# dac0808.net
KiCad netlist of a schematic drawn in Altium Designer
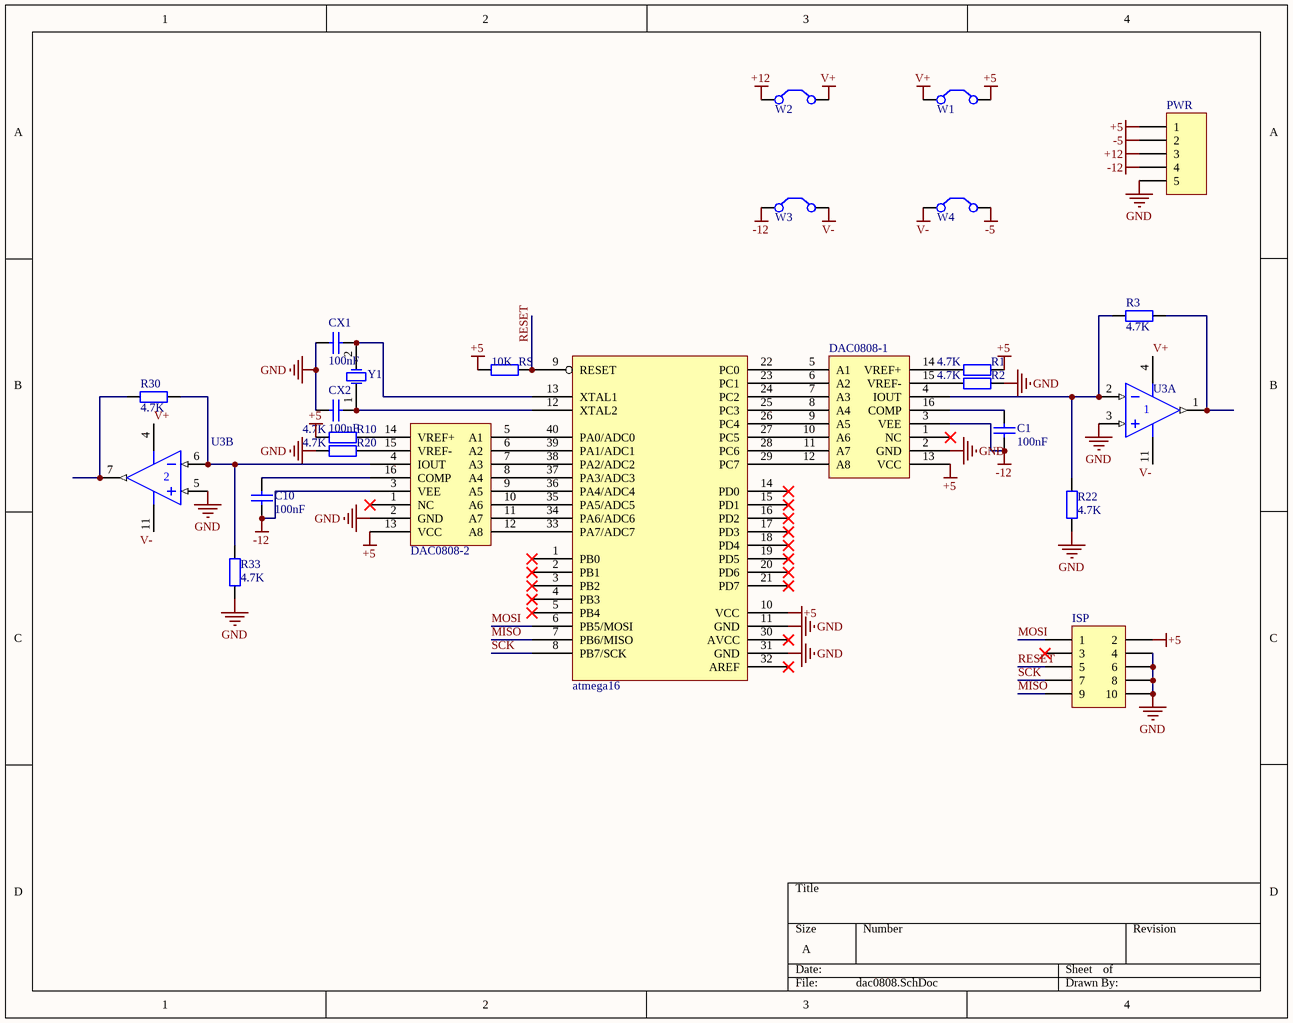
[diagram p0: dac0808.SchDoc]

(export (version "E")
  (design (tool "Eeschema 10.0.6"))
  (components
    (comp (ref "atmega16")
      (value "atmega16")
      (footprint "DIP-40PIN")
      (libsource (lib "atmega16") (part "atmega16"))
    )
    (comp (ref "C1")
      (value "100nF")
      (footprint "mkt")
      (description "Capacitor")
      (fields (field (name "Comment") "Cap") (field (name "PUBLISHER") "Altium Limited"))
      (libsource (lib "Miscellaneous Devices") (part "Cap"))
    )
    (comp (ref "C10")
      (value "100nF")
      (footprint "mkt")
      (description "Capacitor")
      (fields (field (name "Comment") "Cap") (field (name "PUBLISHER") "Altium Limited"))
      (libsource (lib "Miscellaneous Devices") (part "Cap"))
    )
    (comp (ref "CX1")
      (value "100nF")
      (footprint "mkt")
      (description "Capacitor")
      (fields (field (name "Comment") "Cap") (field (name "PUBLISHER") "Altium Limited"))
      (libsource (lib "Miscellaneous Devices") (part "Cap"))
    )
    (comp (ref "CX2")
      (value "100nF")
      (footprint "mkt")
      (description "Capacitor")
      (fields (field (name "Comment") "Cap") (field (name "PUBLISHER") "Altium Limited"))
      (libsource (lib "Miscellaneous Devices") (part "Cap"))
    )
    (comp (ref "DAC0808-1")
      (value "DAC0808")
      (footprint "DIP-16-1")
      (libsource (lib "DAC0808") (part "DAC0808"))
    )
    (comp (ref "DAC0808-2") (value "DAC0808") (footprint "DIP-16-1") (libsource (lib "") (part "DAC0808_1")))
    (comp (ref "ISP")
      (value "Header 5X2")
      (footprint "HDR2X5")
      (description "Header, 5-Pin, Dual row")
      (fields (field (name "PUBLISHER") "Altium Limited"))
      (libsource (lib "Miscellaneous Connectors") (part "Header 5X2"))
    )
    (comp (ref "PWR")
      (value "Header 5")
      (footprint "PWR")
      (description "Header, 5-Pin")
      (fields (field (name "PUBLISHER") "Altium Limited"))
      (libsource (lib "Miscellaneous Connectors") (part "Header 5"))
    )
    (comp (ref "R1")
      (value "4.7K")
      (footprint "AXIAL-0.4")
      (description "Resistor")
      (fields (field (name "Comment") "Res2") (field (name "PUBLISHER") "Altium Limited"))
      (libsource (lib "Miscellaneous Devices") (part "Res2"))
    )
    (comp (ref "R2")
      (value "4.7K")
      (footprint "AXIAL-0.4")
      (description "Resistor")
      (fields (field (name "Comment") "Res2") (field (name "PUBLISHER") "Altium Limited"))
      (libsource (lib "Miscellaneous Devices") (part "Res2"))
    )
    (comp (ref "R3")
      (value "4.7K")
      (footprint "AXIAL-0.4")
      (description "Resistor")
      (fields (field (name "Comment") "Res2") (field (name "PUBLISHER") "Altium Limited"))
      (libsource (lib "Miscellaneous Devices") (part "Res2"))
    )
    (comp (ref "R10")
      (value "4.7K")
      (footprint "AXIAL-0.4")
      (description "Resistor")
      (fields (field (name "Comment") "Res2") (field (name "PUBLISHER") "Altium Limited"))
      (libsource (lib "Miscellaneous Devices") (part "Res2"))
    )
    (comp (ref "R20")
      (value "4.7K")
      (footprint "AXIAL-0.4")
      (description "Resistor")
      (fields (field (name "Comment") "Res2") (field (name "PUBLISHER") "Altium Limited"))
      (libsource (lib "Miscellaneous Devices") (part "Res2"))
    )
    (comp (ref "R22")
      (value "4.7K")
      (footprint "AXIAL-0.4")
      (description "Resistor")
      (fields (field (name "Comment") "Res2") (field (name "PUBLISHER") "Altium Limited"))
      (libsource (lib "") (part "Res2_1"))
    )
    (comp (ref "R30")
      (value "4.7K")
      (footprint "AXIAL-0.4")
      (description "Resistor")
      (fields (field (name "Comment") "Res2") (field (name "PUBLISHER") "Altium Limited"))
      (libsource (lib "Miscellaneous Devices") (part "Res2"))
    )
    (comp (ref "R33")
      (value "4.7K")
      (footprint "AXIAL-0.4")
      (description "Resistor")
      (fields (field (name "Comment") "Res2") (field (name "PUBLISHER") "Altium Limited"))
      (libsource (lib "") (part "Res2_1"))
    )
    (comp (ref "RS")
      (value "10K")
      (footprint "AXIAL-0.4")
      (description "Resistor")
      (fields (field (name "Comment") "Res2") (field (name "PUBLISHER") "Altium Limited"))
      (libsource (lib "Miscellaneous Devices") (part "Res2"))
    )
    (comp (ref "U3")
      (value "LM324AJ")
      (footprint "J014")
      (description "Quadruple Operational Amplifier")
      (fields (field (name "PUBLISHER") "Altium Limited"))
      (libsource (lib "TI Operational Amplifier") (part "LM324AJ"))
    )
    (comp (ref "W1")
      (value "Jumper")
      (footprint "Miscellaneous Connectors:HDR1X2")
      (description "Jumper Wire")
      (fields (field (name "PUBLISHER") "Altium Limited"))
      (libsource (lib "Miscellaneous Devices") (part "Jumper"))
    )
    (comp (ref "W2")
      (value "Jumper")
      (footprint "Miscellaneous Connectors:HDR1X2")
      (description "Jumper Wire")
      (fields (field (name "PUBLISHER") "Altium Limited"))
      (libsource (lib "Miscellaneous Devices") (part "Jumper"))
    )
    (comp (ref "W3")
      (value "Jumper")
      (footprint "Miscellaneous Connectors:HDR1X2")
      (description "Jumper Wire")
      (fields (field (name "PUBLISHER") "Altium Limited"))
      (libsource (lib "Miscellaneous Devices") (part "Jumper"))
    )
    (comp (ref "W4")
      (value "Jumper")
      (footprint "Miscellaneous Connectors:HDR1X2")
      (description "Jumper Wire")
      (fields (field (name "PUBLISHER") "Altium Limited"))
      (libsource (lib "Miscellaneous Devices") (part "Jumper"))
    )
    (comp (ref "Y1")
      (value "XTAL")
      (footprint "XTAL")
      (description "Crystal Oscillator")
      (fields (field (name "PUBLISHER") "Altium Limited"))
      (libsource (lib "Miscellaneous Devices") (part "XTAL"))
    )
  )
  (nets
    (net (code "1") (name "+5") (class "Default")
      (node (ref "DAC0808-1") (pin "13") (pinfunction "VCC_13") (pintype "passive"))
      (node (ref "DAC0808-2") (pin "13") (pinfunction "VCC_13") (pintype "passive"))
      (node (ref "ISP") (pin "2") (pinfunction "2_2") (pintype "passive"))
      (node (ref "PWR") (pin "1") (pinfunction "1_1") (pintype "passive"))
      (node (ref "R1") (pin "2") (pinfunction "2_2") (pintype "passive"))
      (node (ref "R10") (pin "1") (pinfunction "1_1") (pintype "passive"))
      (node (ref "RS") (pin "1") (pinfunction "1_1") (pintype "passive"))
      (node (ref "W1") (pin "2") (pinfunction "C2_2") (pintype "passive"))
      (node (ref "atmega16") (pin "10") (pinfunction "VCC_10") (pintype "passive"))
    )
    (net (code "2") (name "+12") (class "Default")
      (node (ref "PWR") (pin "3") (pinfunction "3_3") (pintype "passive"))
      (node (ref "W2") (pin "1") (pinfunction "C1_1") (pintype "passive"))
    )
    (net (code "3") (name "-5") (class "Default")
      (node (ref "PWR") (pin "2") (pinfunction "2_2") (pintype "passive"))
      (node (ref "W4") (pin "2") (pinfunction "C2_2") (pintype "passive"))
    )
    (net (code "4") (name "-12") (class "Default")
      (node (ref "C1") (pin "1") (pinfunction "1_1") (pintype "passive"))
      (node (ref "C10") (pin "1") (pinfunction "1_1") (pintype "passive"))
      (node (ref "DAC0808-1") (pin "3") (pinfunction "VEE_3") (pintype "passive"))
      (node (ref "DAC0808-2") (pin "3") (pinfunction "VEE_3") (pintype "passive"))
      (node (ref "PWR") (pin "4") (pinfunction "4_4") (pintype "passive"))
      (node (ref "W3") (pin "1") (pinfunction "C1_1") (pintype "passive"))
    )
    (net (code "5") (name "/MISO") (class "Default")
      (node (ref "ISP") (pin "9") (pinfunction "9_9") (pintype "passive"))
      (node (ref "atmega16") (pin "7") (pinfunction "PB6/MISO_7") (pintype "passive"))
    )
    (net (code "6") (name "/MOSI") (class "Default")
      (node (ref "ISP") (pin "1") (pinfunction "1_1") (pintype "passive"))
      (node (ref "atmega16") (pin "6") (pinfunction "PB5/MOSI_6") (pintype "passive"))
    )
    (net (code "7") (name "/RESET") (class "Default")
      (node (ref "ISP") (pin "5") (pinfunction "5_5") (pintype "passive"))
      (node (ref "RS") (pin "2") (pinfunction "2_2") (pintype "passive"))
      (node (ref "atmega16") (pin "9") (pinfunction "RESET_9") (pintype "passive"))
    )
    (net (code "8") (name "/SCK") (class "Default")
      (node (ref "ISP") (pin "7") (pinfunction "7_7") (pintype "passive"))
      (node (ref "atmega16") (pin "8") (pinfunction "PB7/SCK_8") (pintype "passive"))
    )
    (net (code "9") (name "GND") (class "Default")
      (node (ref "CX1") (pin "1") (pinfunction "1_1") (pintype "passive"))
      (node (ref "CX2") (pin "1") (pinfunction "1_1") (pintype "passive"))
      (node (ref "DAC0808-1") (pin "2") (pinfunction "GND_2") (pintype "passive"))
      (node (ref "DAC0808-2") (pin "2") (pinfunction "GND_2") (pintype "passive"))
      (node (ref "ISP") (pin "10") (pinfunction "10_10") (pintype "passive"))
      (node (ref "ISP") (pin "4") (pinfunction "4_4") (pintype "passive"))
      (node (ref "ISP") (pin "6") (pinfunction "6_6") (pintype "passive"))
      (node (ref "ISP") (pin "8") (pinfunction "8_8") (pintype "passive"))
      (node (ref "PWR") (pin "5") (pinfunction "5_5") (pintype "passive"))
      (node (ref "R2") (pin "2") (pinfunction "2_2") (pintype "passive"))
      (node (ref "R20") (pin "1") (pinfunction "1_1") (pintype "passive"))
      (node (ref "R22") (pin "1") (pinfunction "1_1") (pintype "passive"))
      (node (ref "R33") (pin "1") (pinfunction "1_1") (pintype "passive"))
      (node (ref "U3") (pin "3") (pinfunction "IN+_3") (pintype "input"))
      (node (ref "U3") (pin "5") (pinfunction "IN+_5") (pintype "input"))
      (node (ref "atmega16") (pin "11") (pinfunction "GND_11") (pintype "passive"))
      (node (ref "atmega16") (pin "31") (pinfunction "GND_31") (pintype "passive"))
    )
    (net (code "10") (name "Net-(DAC0808-1-A1)") (class "Default")
      (node (ref "DAC0808-1") (pin "5") (pinfunction "A1_5") (pintype "passive"))
      (node (ref "atmega16") (pin "22") (pinfunction "PC0_22") (pintype "passive"))
    )
    (net (code "11") (name "Net-(DAC0808-1-A2)") (class "Default")
      (node (ref "DAC0808-1") (pin "6") (pinfunction "A2_6") (pintype "passive"))
      (node (ref "atmega16") (pin "23") (pinfunction "PC1_23") (pintype "passive"))
    )
    (net (code "12") (name "Net-(DAC0808-1-A3)") (class "Default")
      (node (ref "DAC0808-1") (pin "7") (pinfunction "A3_7") (pintype "passive"))
      (node (ref "atmega16") (pin "24") (pinfunction "PC2_24") (pintype "passive"))
    )
    (net (code "13") (name "Net-(DAC0808-1-A4)") (class "Default")
      (node (ref "DAC0808-1") (pin "8") (pinfunction "A4_8") (pintype "passive"))
      (node (ref "atmega16") (pin "25") (pinfunction "PC3_25") (pintype "passive"))
    )
    (net (code "14") (name "Net-(DAC0808-1-A5)") (class "Default")
      (node (ref "DAC0808-1") (pin "9") (pinfunction "A5_9") (pintype "passive"))
      (node (ref "atmega16") (pin "26") (pinfunction "PC4_26") (pintype "passive"))
    )
    (net (code "15") (name "Net-(DAC0808-1-A6)") (class "Default")
      (node (ref "DAC0808-1") (pin "10") (pinfunction "A6_10") (pintype "passive"))
      (node (ref "atmega16") (pin "27") (pinfunction "PC5_27") (pintype "passive"))
    )
    (net (code "16") (name "Net-(DAC0808-1-A7)") (class "Default")
      (node (ref "DAC0808-1") (pin "11") (pinfunction "A7_11") (pintype "passive"))
      (node (ref "atmega16") (pin "28") (pinfunction "PC6_28") (pintype "passive"))
    )
    (net (code "17") (name "Net-(DAC0808-1-A8)") (class "Default")
      (node (ref "DAC0808-1") (pin "12") (pinfunction "A8_12") (pintype "passive"))
      (node (ref "atmega16") (pin "29") (pinfunction "PC7_29") (pintype "passive"))
    )
    (net (code "18") (name "Net-(DAC0808-1-COMP)") (class "Default")
      (node (ref "C1") (pin "2") (pinfunction "2_2") (pintype "passive"))
      (node (ref "DAC0808-1") (pin "16") (pinfunction "COMP_16") (pintype "passive"))
    )
    (net (code "19") (name "Net-(DAC0808-1-IOUT)") (class "Default")
      (node (ref "DAC0808-1") (pin "4") (pinfunction "IOUT_4") (pintype "passive"))
      (node (ref "R22") (pin "2") (pinfunction "2_2") (pintype "passive"))
      (node (ref "R3") (pin "1") (pinfunction "1_1") (pintype "passive"))
      (node (ref "U3") (pin "2") (pinfunction "IN-_2") (pintype "input"))
    )
    (net (code "20") (name "Net-(DAC0808-1-VREF+)") (class "Default")
      (node (ref "DAC0808-1") (pin "14") (pinfunction "VREF+_14") (pintype "passive"))
      (node (ref "R1") (pin "1") (pinfunction "1_1") (pintype "passive"))
    )
    (net (code "21") (name "Net-(DAC0808-1-VREF-)") (class "Default")
      (node (ref "DAC0808-1") (pin "15") (pinfunction "VREF-_15") (pintype "passive"))
      (node (ref "R2") (pin "1") (pinfunction "1_1") (pintype "passive"))
    )
    (net (code "22") (name "Net-(DAC0808-2-A1)") (class "Default")
      (node (ref "DAC0808-2") (pin "5") (pinfunction "A1_5") (pintype "passive"))
      (node (ref "atmega16") (pin "40") (pinfunction "PA0/ADC0_40") (pintype "passive"))
    )
    (net (code "23") (name "Net-(DAC0808-2-A2)") (class "Default")
      (node (ref "DAC0808-2") (pin "6") (pinfunction "A2_6") (pintype "passive"))
      (node (ref "atmega16") (pin "39") (pinfunction "PA1/ADC1_39") (pintype "passive"))
    )
    (net (code "24") (name "Net-(DAC0808-2-A3)") (class "Default")
      (node (ref "DAC0808-2") (pin "7") (pinfunction "A3_7") (pintype "passive"))
      (node (ref "atmega16") (pin "38") (pinfunction "PA2/ADC2_38") (pintype "passive"))
    )
    (net (code "25") (name "Net-(DAC0808-2-A4)") (class "Default")
      (node (ref "DAC0808-2") (pin "8") (pinfunction "A4_8") (pintype "passive"))
      (node (ref "atmega16") (pin "37") (pinfunction "PA3/ADC3_37") (pintype "passive"))
    )
    (net (code "26") (name "Net-(DAC0808-2-A5)") (class "Default")
      (node (ref "DAC0808-2") (pin "9") (pinfunction "A5_9") (pintype "passive"))
      (node (ref "atmega16") (pin "36") (pinfunction "PA4/ADC4_36") (pintype "passive"))
    )
    (net (code "27") (name "Net-(DAC0808-2-A6)") (class "Default")
      (node (ref "DAC0808-2") (pin "10") (pinfunction "A6_10") (pintype "passive"))
      (node (ref "atmega16") (pin "35") (pinfunction "PA5/ADC5_35") (pintype "passive"))
    )
    (net (code "28") (name "Net-(DAC0808-2-A7)") (class "Default")
      (node (ref "DAC0808-2") (pin "11") (pinfunction "A7_11") (pintype "passive"))
      (node (ref "atmega16") (pin "34") (pinfunction "PA6/ADC6_34") (pintype "passive"))
    )
    (net (code "29") (name "Net-(DAC0808-2-A8)") (class "Default")
      (node (ref "DAC0808-2") (pin "12") (pinfunction "A8_12") (pintype "passive"))
      (node (ref "atmega16") (pin "33") (pinfunction "PA7/ADC7_33") (pintype "passive"))
    )
    (net (code "30") (name "Net-(DAC0808-2-COMP)") (class "Default")
      (node (ref "C10") (pin "2") (pinfunction "2_2") (pintype "passive"))
      (node (ref "DAC0808-2") (pin "16") (pinfunction "COMP_16") (pintype "passive"))
    )
    (net (code "31") (name "Net-(DAC0808-2-IOUT)") (class "Default")
      (node (ref "DAC0808-2") (pin "4") (pinfunction "IOUT_4") (pintype "passive"))
      (node (ref "R30") (pin "2") (pinfunction "2_2") (pintype "passive"))
      (node (ref "R33") (pin "2") (pinfunction "2_2") (pintype "passive"))
      (node (ref "U3") (pin "6") (pinfunction "IN-_6") (pintype "input"))
    )
    (net (code "32") (name "Net-(DAC0808-2-VREF+)") (class "Default")
      (node (ref "DAC0808-2") (pin "14") (pinfunction "VREF+_14") (pintype "passive"))
      (node (ref "R10") (pin "2") (pinfunction "2_2") (pintype "passive"))
    )
    (net (code "33") (name "Net-(DAC0808-2-VREF-)") (class "Default")
      (node (ref "DAC0808-2") (pin "15") (pinfunction "VREF-_15") (pintype "passive"))
      (node (ref "R20") (pin "2") (pinfunction "2_2") (pintype "passive"))
    )
    (net (code "34") (name "Net-(U3A-OUT)") (class "Default")
      (node (ref "R3") (pin "2") (pinfunction "2_2") (pintype "passive"))
      (node (ref "U3") (pin "1") (pinfunction "OUT_1") (pintype "output"))
    )
    (net (code "35") (name "Net-(U3B-OUT)") (class "Default")
      (node (ref "R30") (pin "1") (pinfunction "1_1") (pintype "passive"))
      (node (ref "U3") (pin "7") (pinfunction "OUT_7") (pintype "output"))
    )
    (net (code "36") (name "Net-(Y1-OSC1)") (class "Default")
      (node (ref "CX2") (pin "2") (pinfunction "2_2") (pintype "passive"))
      (node (ref "Y1") (pin "1") (pinfunction "OSC1_1") (pintype "passive"))
      (node (ref "atmega16") (pin "12") (pinfunction "XTAL2_12") (pintype "passive"))
    )
    (net (code "37") (name "Net-(Y1-OSC2)") (class "Default")
      (node (ref "CX1") (pin "2") (pinfunction "2_2") (pintype "passive"))
      (node (ref "Y1") (pin "2") (pinfunction "OSC2_2") (pintype "passive"))
      (node (ref "atmega16") (pin "13") (pinfunction "XTAL1_13") (pintype "passive"))
    )
    (net (code "38") (name "V+") (class "Default")
      (node (ref "U3") (pin "4") (pinfunction "V+_4") (pintype "power_in"))
      (node (ref "W1") (pin "1") (pinfunction "C1_1") (pintype "passive"))
      (node (ref "W2") (pin "2") (pinfunction "C2_2") (pintype "passive"))
    )
    (net (code "39") (name "V-") (class "Default")
      (node (ref "U3") (pin "11") (pinfunction "V-_11") (pintype "power_in"))
      (node (ref "W3") (pin "2") (pinfunction "C2_2") (pintype "passive"))
      (node (ref "W4") (pin "1") (pinfunction "C1_1") (pintype "passive"))
    )
    (net (code "40") (name "unconnected-(DAC0808-1-NC-Pad1)") (class "Default")
      (node (ref "DAC0808-1") (pin "1") (pinfunction "NC_1") (pintype "passive+no_connect"))
    )
    (net (code "41") (name "unconnected-(DAC0808-2-NC-Pad1)") (class "Default")
      (node (ref "DAC0808-2") (pin "1") (pinfunction "NC_1") (pintype "passive+no_connect"))
    )
    (net (code "42") (name "unconnected-(ISP-Pad3)") (class "Default")
      (node (ref "ISP") (pin "3") (pinfunction "3_3") (pintype "passive+no_connect"))
    )
    (net (code "43") (name "unconnected-(atmega16-AREF-Pad32)") (class "Default")
      (node (ref "atmega16") (pin "32") (pinfunction "AREF_32") (pintype "passive+no_connect"))
    )
    (net (code "44") (name "unconnected-(atmega16-AVCC-Pad30)") (class "Default")
      (node (ref "atmega16") (pin "30") (pinfunction "AVCC_30") (pintype "passive+no_connect"))
    )
    (net (code "45") (name "unconnected-(atmega16-PB0-Pad1)") (class "Default")
      (node (ref "atmega16") (pin "1") (pinfunction "PB0_1") (pintype "passive+no_connect"))
    )
    (net (code "46") (name "unconnected-(atmega16-PB1-Pad2)") (class "Default")
      (node (ref "atmega16") (pin "2") (pinfunction "PB1_2") (pintype "passive+no_connect"))
    )
    (net (code "47") (name "unconnected-(atmega16-PB2-Pad3)") (class "Default")
      (node (ref "atmega16") (pin "3") (pinfunction "PB2_3") (pintype "passive+no_connect"))
    )
    (net (code "48") (name "unconnected-(atmega16-PB3-Pad4)") (class "Default")
      (node (ref "atmega16") (pin "4") (pinfunction "PB3_4") (pintype "passive+no_connect"))
    )
    (net (code "49") (name "unconnected-(atmega16-PB4-Pad5)") (class "Default")
      (node (ref "atmega16") (pin "5") (pinfunction "PB4_5") (pintype "passive+no_connect"))
    )
    (net (code "50") (name "unconnected-(atmega16-PD0-Pad14)") (class "Default")
      (node (ref "atmega16") (pin "14") (pinfunction "PD0_14") (pintype "passive+no_connect"))
    )
    (net (code "51") (name "unconnected-(atmega16-PD1-Pad15)") (class "Default")
      (node (ref "atmega16") (pin "15") (pinfunction "PD1_15") (pintype "passive+no_connect"))
    )
    (net (code "52") (name "unconnected-(atmega16-PD2-Pad16)") (class "Default")
      (node (ref "atmega16") (pin "16") (pinfunction "PD2_16") (pintype "passive+no_connect"))
    )
    (net (code "53") (name "unconnected-(atmega16-PD3-Pad17)") (class "Default")
      (node (ref "atmega16") (pin "17") (pinfunction "PD3_17") (pintype "passive+no_connect"))
    )
    (net (code "54") (name "unconnected-(atmega16-PD4-Pad18)") (class "Default")
      (node (ref "atmega16") (pin "18") (pinfunction "PD4_18") (pintype "passive+no_connect"))
    )
    (net (code "55") (name "unconnected-(atmega16-PD5-Pad19)") (class "Default")
      (node (ref "atmega16") (pin "19") (pinfunction "PD5_19") (pintype "passive+no_connect"))
    )
    (net (code "56") (name "unconnected-(atmega16-PD6-Pad20)") (class "Default")
      (node (ref "atmega16") (pin "20") (pinfunction "PD6_20") (pintype "passive+no_connect"))
    )
    (net (code "57") (name "unconnected-(atmega16-PD7-Pad21)") (class "Default")
      (node (ref "atmega16") (pin "21") (pinfunction "PD7_21") (pintype "passive+no_connect"))
    )
  )
)
